# Redresseur.net
KiCad netlist of a schematic drawn in Altium Designer
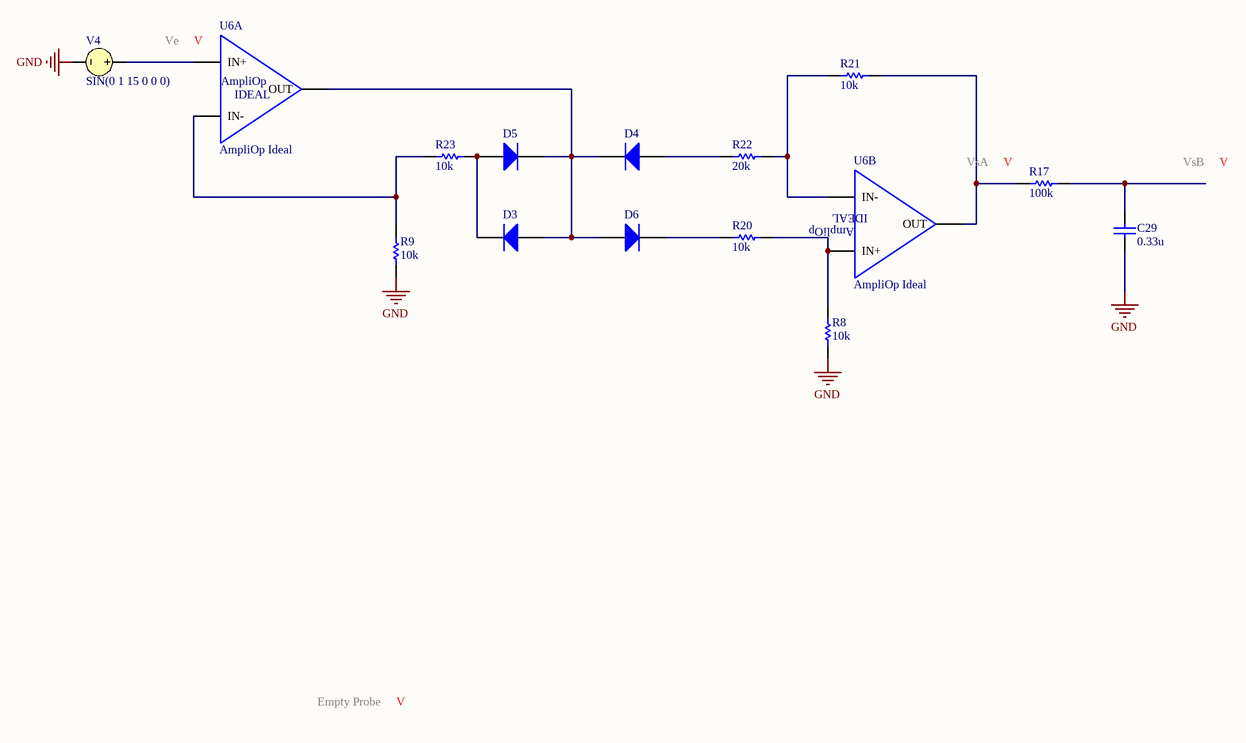
[diagram p0: Redresseur.SchDoc]

(export (version "E")
  (design (tool "Eeschema 10.0.6"))
  (components
    (comp (ref "C29")
      (value "0.33u")
      (description "Capacitor")
      (libsource (lib "Simulation Generic Components") (part "Capacitor"))
    )
    (comp (ref "D3") (value "Diode") (libsource (lib "Simulation Generic Components") (part "Diode")))
    (comp (ref "D4") (value "Diode") (libsource (lib "Simulation Generic Components") (part "Diode")))
    (comp (ref "D5") (value "Diode") (libsource (lib "Simulation Generic Components") (part "Diode")))
    (comp (ref "D6") (value "Diode") (libsource (lib "Simulation Generic Components") (part "Diode")))
    (comp (ref "R8")
      (value "10k")
      (description "Resistor")
      (libsource (lib "Simulation Generic Components") (part "Resistor"))
    )
    (comp (ref "R9")
      (value "10k")
      (description "Resistor")
      (libsource (lib "Simulation Generic Components") (part "Resistor"))
    )
    (comp (ref "R17")
      (value "100k")
      (description "Resistor")
      (libsource (lib "Simulation Generic Components") (part "Resistor"))
    )
    (comp (ref "R20")
      (value "10k")
      (description "Resistor")
      (libsource (lib "Simulation Generic Components") (part "Resistor"))
    )
    (comp (ref "R21")
      (value "10k")
      (description "Resistor")
      (libsource (lib "Simulation Generic Components") (part "Resistor"))
    )
    (comp (ref "R22")
      (value "20k")
      (description "Resistor")
      (libsource (lib "Simulation Generic Components") (part "Resistor"))
    )
    (comp (ref "R23")
      (value "10k")
      (description "Resistor")
      (libsource (lib "Simulation Generic Components") (part "Resistor"))
    )
    (comp (ref "U6A") (value "AmpliOp Ideal") (libsource (lib "Librarie_S2") (part "AmpliOp_ideal")))
    (comp (ref "U6B") (value "AmpliOp Ideal") (libsource (lib "Librarie_S2") (part "AmpliOp_ideal")))
    (comp (ref "V4")
      (value "SIN(0 1 15 0 0 0)")
      (description "Voltage Source")
      (fields (field (name "PUBLISHER") "Altium Limited"))
      (libsource (lib "Simulation Generic Components") (part "VSRC"))
    )
  )
  (nets
    (net (code "1") (name "GND") (class "Default")
      (node (ref "C29") (pin "1") (pinfunction "1_1") (pintype "passive"))
      (node (ref "R8") (pin "1") (pinfunction "1_1") (pintype "passive"))
      (node (ref "R9") (pin "1") (pinfunction "1_1") (pintype "passive"))
      (node (ref "V4") (pin "2") (pinfunction "2_2") (pintype "passive"))
    )
    (net (code "2") (name "Net-(C29-Pad2)") (class "Default")
      (node (ref "C29") (pin "2") (pinfunction "2_2") (pintype "passive"))
      (node (ref "R17") (pin "2") (pinfunction "2_2") (pintype "passive"))
    )
    (net (code "3") (name "Net-(D3-A)") (class "Default")
      (node (ref "D3") (pin "1") (pinfunction "A_1") (pintype "passive"))
      (node (ref "D4") (pin "2") (pinfunction "K_2") (pintype "passive"))
      (node (ref "D5") (pin "2") (pinfunction "K_2") (pintype "passive"))
      (node (ref "D6") (pin "1") (pinfunction "A_1") (pintype "passive"))
      (node (ref "U6A") (pin "3") (pinfunction "OUT_3") (pintype "passive"))
    )
    (net (code "4") (name "Net-(D3-K)") (class "Default")
      (node (ref "D3") (pin "2") (pinfunction "K_2") (pintype "passive"))
      (node (ref "D5") (pin "1") (pinfunction "A_1") (pintype "passive"))
      (node (ref "R23") (pin "2") (pinfunction "2_2") (pintype "passive"))
    )
    (net (code "5") (name "Net-(D4-A)") (class "Default")
      (node (ref "D4") (pin "1") (pinfunction "A_1") (pintype "passive"))
      (node (ref "R22") (pin "1") (pinfunction "1_1") (pintype "passive"))
    )
    (net (code "6") (name "Net-(D6-K)") (class "Default")
      (node (ref "D6") (pin "2") (pinfunction "K_2") (pintype "passive"))
      (node (ref "R20") (pin "1") (pinfunction "1_1") (pintype "passive"))
    )
    (net (code "7") (name "Net-(U6A-IN+)") (class "Default")
      (node (ref "U6A") (pin "1") (pinfunction "IN+_1") (pintype "passive"))
      (node (ref "V4") (pin "1") (pinfunction "1_1") (pintype "passive"))
    )
    (net (code "8") (name "Net-(U6A-IN-)") (class "Default")
      (node (ref "R23") (pin "1") (pinfunction "1_1") (pintype "passive"))
      (node (ref "R9") (pin "2") (pinfunction "2_2") (pintype "passive"))
      (node (ref "U6A") (pin "2") (pinfunction "IN-_2") (pintype "passive"))
    )
    (net (code "9") (name "Net-(U6B-IN+)") (class "Default")
      (node (ref "R20") (pin "2") (pinfunction "2_2") (pintype "passive"))
      (node (ref "R8") (pin "2") (pinfunction "2_2") (pintype "passive"))
      (node (ref "U6B") (pin "1") (pinfunction "IN+_1") (pintype "passive"))
    )
    (net (code "10") (name "Net-(U6B-IN-)") (class "Default")
      (node (ref "R21") (pin "1") (pinfunction "1_1") (pintype "passive"))
      (node (ref "R22") (pin "2") (pinfunction "2_2") (pintype "passive"))
      (node (ref "U6B") (pin "2") (pinfunction "IN-_2") (pintype "passive"))
    )
    (net (code "11") (name "Net-(U6B-OUT)") (class "Default")
      (node (ref "R17") (pin "1") (pinfunction "1_1") (pintype "passive"))
      (node (ref "R21") (pin "2") (pinfunction "2_2") (pintype "passive"))
      (node (ref "U6B") (pin "3") (pinfunction "OUT_3") (pintype "passive"))
    )
  )
)
